# AnalogReceiverModule.net
KiCad netlist of a schematic drawn in Altium Designer
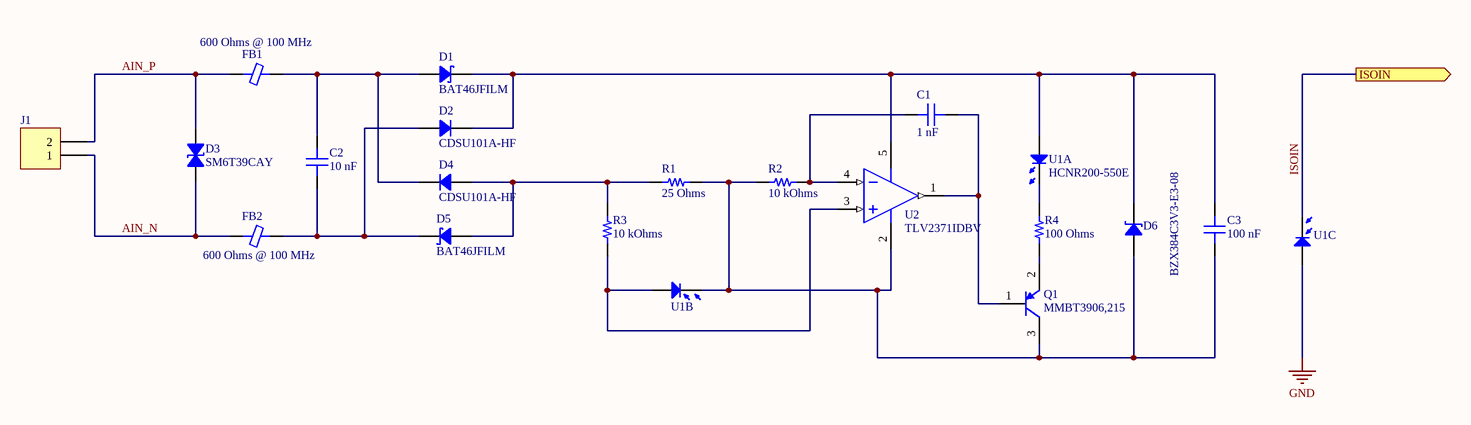
[diagram p0: AnalogReceiverModule.SchDoc]

(export (version "E")
  (design (tool "Eeschema 10.0.6"))
  (components
    (comp (ref "C1")
      (value "1 nF")
      (footprint "CAP 0805_2012")
      (description "MLCC Ceramic 1 nF 200 V 5% Capacitor")
      (fields (field (name "PART NUMBER") "C0805C102J2GECAUTO") (field (name "MANUFACTURER") "KEMET"))
      (libsource (lib "Database_Libs") (part "Capacitor"))
    )
    (comp (ref "C2")
      (value "10 nF")
      (footprint "CAP 0805_2012")
      (description "MLCC Ceramic 10 nF 50 V 10% Capacitor")
      (fields (field (name "PART NUMBER") "C0805C103K5GEC7210") (field (name "MANUFACTURER") "KEMET"))
      (libsource (lib "Database_Libs") (part "Capacitor"))
    )
    (comp (ref "C3")
      (value "100 nF")
      (footprint "CAP 0805_2012")
      (description "MLCC Ceramic 100 nF 50 V 10% Capacitor")
      (fields (field (name "PART NUMBER") "08055C104K4Z2A") (field (name "MANUFACTURER") "AVX"))
      (libsource (lib "Database_Libs") (part "Capacitor"))
    )
    (comp (ref "D1")
      (value "BAT46JFILM")
      (footprint "SOD323")
      (description "Schottky Diode")
      (fields (field (name "MANUFACTURER") "STMicroelectronics"))
      (libsource (lib "Database_Libs") (part "Schottky"))
    )
    (comp (ref "D2")
      (value "CDSU101A-HF")
      (footprint "SOD523F")
      (description "General Purpose Diode")
      (fields (field (name "MANUFACTURER") "Comchip Technology"))
      (libsource (lib "Database_Libs") (part "Diode"))
    )
    (comp (ref "D3")
      (value "SM6T39CAY")
      (footprint "DO214AA SMB")
      (description "TVS Diode")
      (fields (field (name "MANUFACTURER") "STMicroelectronics"))
      (libsource (lib "Database_Libs") (part "Diode TVS"))
    )
    (comp (ref "D4")
      (value "CDSU101A-HF")
      (footprint "SOD523F")
      (description "General Purpose Diode")
      (fields (field (name "MANUFACTURER") "Comchip Technology"))
      (libsource (lib "Database_Libs") (part "Diode"))
    )
    (comp (ref "D5")
      (value "BAT46JFILM")
      (footprint "SOD323")
      (description "Schottky Diode")
      (fields (field (name "MANUFACTURER") "STMicroelectronics"))
      (libsource (lib "Database_Libs") (part "Schottky"))
    )
    (comp (ref "D6")
      (value "BZX384C3V3-E3-08")
      (footprint "SOD323")
      (description "Zener Diode 3.3 V 200 mW")
      (fields (field (name "MANUFACTURER") "Vishay") (field (name "TOLERANCE") "5%"))
      (libsource (lib "Database_Libs") (part "Diode Zener"))
    )
    (comp (ref "FB1")
      (value "600 Ohms @ 100 MHz")
      (footprint "FER 0805_2012")
      (description "Ferrite bead")
      (fields
        (field (name "PART NUMBER") "BLM21SP601SH1D")
        (field (name "MANUFACTURER") "Murata Electronics")
      )
      (libsource (lib "Database_Libs") (part "Ferrite Chip"))
    )
    (comp (ref "FB2")
      (value "600 Ohms @ 100 MHz")
      (footprint "FER 0805_2012")
      (description "Ferrite bead")
      (fields
        (field (name "PART NUMBER") "BLM21SP601SH1D")
        (field (name "MANUFACTURER") "Murata Electronics")
      )
      (libsource (lib "Database_Libs") (part "Ferrite Chip"))
    )
    (comp (ref "J1")
      (value "1757475")
      (footprint "MSTBA2")
      (description "Pluggable Terminal Blocks 2 Pos 5mm pitch Through Hole Header")
      (fields (field (name "MANUFACTURER") "Phoenix Contact") (field (name "PUBLISHER") "Altium Limited"))
      (libsource (lib "Database_Libs") (part "GEN-2-CON"))
    )
    (comp (ref "Q1")
      (value "MMBT3906,215")
      (footprint "NEXPERIA SOT-23-3")
      (description "PNP BJT Switching transistor")
      (fields (field (name "MANUFACTURER") "Nexperia"))
      (libsource (lib "Database_Libs") (part "PNP SOT-23-3"))
    )
    (comp (ref "R1")
      (value "25 Ohms")
      (footprint "RES 0805_2012")
      (description "Thin Film Resistor 25 Ohms 0.1%")
      (fields (field (name "PART NUMBER") "PAT0805E25R0BST1") (field (name "MANUFACTURER") "Vishay"))
      (libsource (lib "Database_Libs") (part "Resistor"))
    )
    (comp (ref "R2")
      (value "10 kOhms")
      (footprint "RES 0805_2012")
      (description "Thin Film Resistor 10 kOhms 1%")
      (fields (field (name "PART NUMBER") "CRCW080510K0FKEAC") (field (name "MANUFACTURER") "Vishay / Dale"))
      (libsource (lib "Database_Libs") (part "Resistor"))
    )
    (comp (ref "R3")
      (value "10 kOhms")
      (footprint "RES 0805_2012")
      (description "Thin Film Resistor 10 kOhms 1%")
      (fields (field (name "PART NUMBER") "CRCW080510K0FKEAC") (field (name "MANUFACTURER") "Vishay / Dale"))
      (libsource (lib "Database_Libs") (part "Resistor"))
    )
    (comp (ref "R4")
      (value "100 Ohms")
      (footprint "RES 0805_2012")
      (description "Thin Film Resistor 100 Ohms 1%")
      (fields (field (name "PART NUMBER") "CRCW0805100RFKEAC") (field (name "MANUFACTURER") "Vishay / Dale"))
      (libsource (lib "Database_Libs") (part "Resistor"))
    )
    (comp (ref "U1")
      (value "HCNR200-550E")
      (footprint "HCNR200")
      (description "HCNR200 High-Linearity Analog Optocoupler")
      (fields (field (name "MANUFACTURER") "Broadcom / Avago"))
      (libsource (lib "Database_Libs") (part "LINEAR OPTOCOUPLER"))
    )
    (comp (ref "U2")
      (value "TLV2371IDBV")
      (footprint "TI SOT-23-5 DBV")
      (description "TLV2371 Rail-to-Rail I/O Opamp")
      (fields (field (name "MANUFACTURER") "Texas Instruments"))
      (libsource (lib "Database_Libs") (part "TLV2371"))
    )
  )
  (nets
    (net (code "1") (name "/AIN_N") (class "Default")
      (node (ref "D3") (pin "2") (pinfunction "2_2") (pintype "passive"))
      (node (ref "FB2") (pin "2") (pinfunction "2_2") (pintype "passive"))
      (node (ref "J1") (pin "1") (pinfunction "1_1") (pintype "passive"))
    )
    (net (code "2") (name "/AIN_P") (class "Default")
      (node (ref "D3") (pin "1") (pinfunction "1_1") (pintype "passive"))
      (node (ref "FB1") (pin "1") (pinfunction "1_1") (pintype "passive"))
      (node (ref "J1") (pin "2") (pinfunction "2_2") (pintype "passive"))
    )
    (net (code "3") (name "/ISOIN") (class "Default")
      (node (ref "U1") (pin "6") (pinfunction "PD2_A_6") (pintype "passive"))
    )
    (net (code "4") (name "GND") (class "Default")
      (node (ref "U1") (pin "5") (pinfunction "PD2_B_5") (pintype "passive"))
    )
    (net (code "5") (name "Net-(C2-Pad1)") (class "Default")
      (node (ref "C2") (pin "1") (pinfunction "1_1") (pintype "passive"))
      (node (ref "D2") (pin "1") (pinfunction "1_1") (pintype "passive"))
      (node (ref "D5") (pin "2") (pinfunction "2_2") (pintype "passive"))
      (node (ref "FB2") (pin "1") (pinfunction "1_1") (pintype "passive"))
    )
    (net (code "6") (name "Net-(C2-Pad2)") (class "Default")
      (node (ref "C2") (pin "2") (pinfunction "2_2") (pintype "passive"))
      (node (ref "D1") (pin "1") (pinfunction "1_1") (pintype "passive"))
      (node (ref "D4") (pin "2") (pinfunction "2_2") (pintype "passive"))
      (node (ref "FB1") (pin "2") (pinfunction "2_2") (pintype "passive"))
    )
    (net (code "7") (name "Net-(D4-Pad1)") (class "Default")
      (node (ref "D4") (pin "1") (pinfunction "1_1") (pintype "passive"))
      (node (ref "D5") (pin "1") (pinfunction "1_1") (pintype "passive"))
      (node (ref "R1") (pin "1") (pinfunction "1_1") (pintype "passive"))
      (node (ref "R3") (pin "1") (pinfunction "1_1") (pintype "passive"))
    )
    (net (code "8") (name "Net-(Q1-B)") (class "Default")
      (node (ref "C1") (pin "1") (pinfunction "1_1") (pintype "passive"))
      (node (ref "Q1") (pin "1") (pinfunction "B_1") (pintype "passive"))
      (node (ref "U2") (pin "1") (pinfunction "OUT_1") (pintype "output"))
    )
    (net (code "9") (name "Net-(Q1-C)") (class "Default")
      (node (ref "C3") (pin "1") (pinfunction "1_1") (pintype "passive"))
      (node (ref "D6") (pin "1") (pinfunction "1_1") (pintype "passive"))
      (node (ref "Q1") (pin "3") (pinfunction "C_3") (pintype "passive"))
      (node (ref "R1") (pin "2") (pinfunction "2_2") (pintype "passive"))
      (node (ref "R2") (pin "2") (pinfunction "2_2") (pintype "passive"))
      (node (ref "U1") (pin "3") (pinfunction "PD1_A_3") (pintype "passive"))
      (node (ref "U2") (pin "2") (pinfunction "GND_2") (pintype "power_in"))
    )
    (net (code "10") (name "Net-(Q1-E)") (class "Default")
      (node (ref "Q1") (pin "2") (pinfunction "E_2") (pintype "passive"))
      (node (ref "R4") (pin "2") (pinfunction "2_2") (pintype "passive"))
    )
    (net (code "11") (name "Net-(U1A-LED_1)") (class "Default")
      (node (ref "R4") (pin "1") (pinfunction "1_1") (pintype "passive"))
      (node (ref "U1") (pin "1") (pinfunction "LED_1_1") (pintype "passive"))
    )
    (net (code "12") (name "Net-(U1A-LED_2)") (class "Default")
      (node (ref "C3") (pin "2") (pinfunction "2_2") (pintype "passive"))
      (node (ref "D1") (pin "2") (pinfunction "2_2") (pintype "passive"))
      (node (ref "D2") (pin "2") (pinfunction "2_2") (pintype "passive"))
      (node (ref "D6") (pin "2") (pinfunction "2_2") (pintype "passive"))
      (node (ref "U1") (pin "2") (pinfunction "LED_2_2") (pintype "passive"))
      (node (ref "U2") (pin "5") (pinfunction "VDD_5") (pintype "power_in"))
    )
    (net (code "13") (name "Net-(U1B-PD1_B)") (class "Default")
      (node (ref "R3") (pin "2") (pinfunction "2_2") (pintype "passive"))
      (node (ref "U1") (pin "4") (pinfunction "PD1_B_4") (pintype "passive"))
      (node (ref "U2") (pin "3") (pinfunction "IN+_3") (pintype "input"))
    )
    (net (code "14") (name "Net-(U2-IN-)") (class "Default")
      (node (ref "C1") (pin "2") (pinfunction "2_2") (pintype "passive"))
      (node (ref "R2") (pin "1") (pinfunction "1_1") (pintype "passive"))
      (node (ref "U2") (pin "4") (pinfunction "IN-_4") (pintype "input"))
    )
  )
)
